# 0001_Page_1.net
KiCad netlist of a schematic drawn in Altium Designer
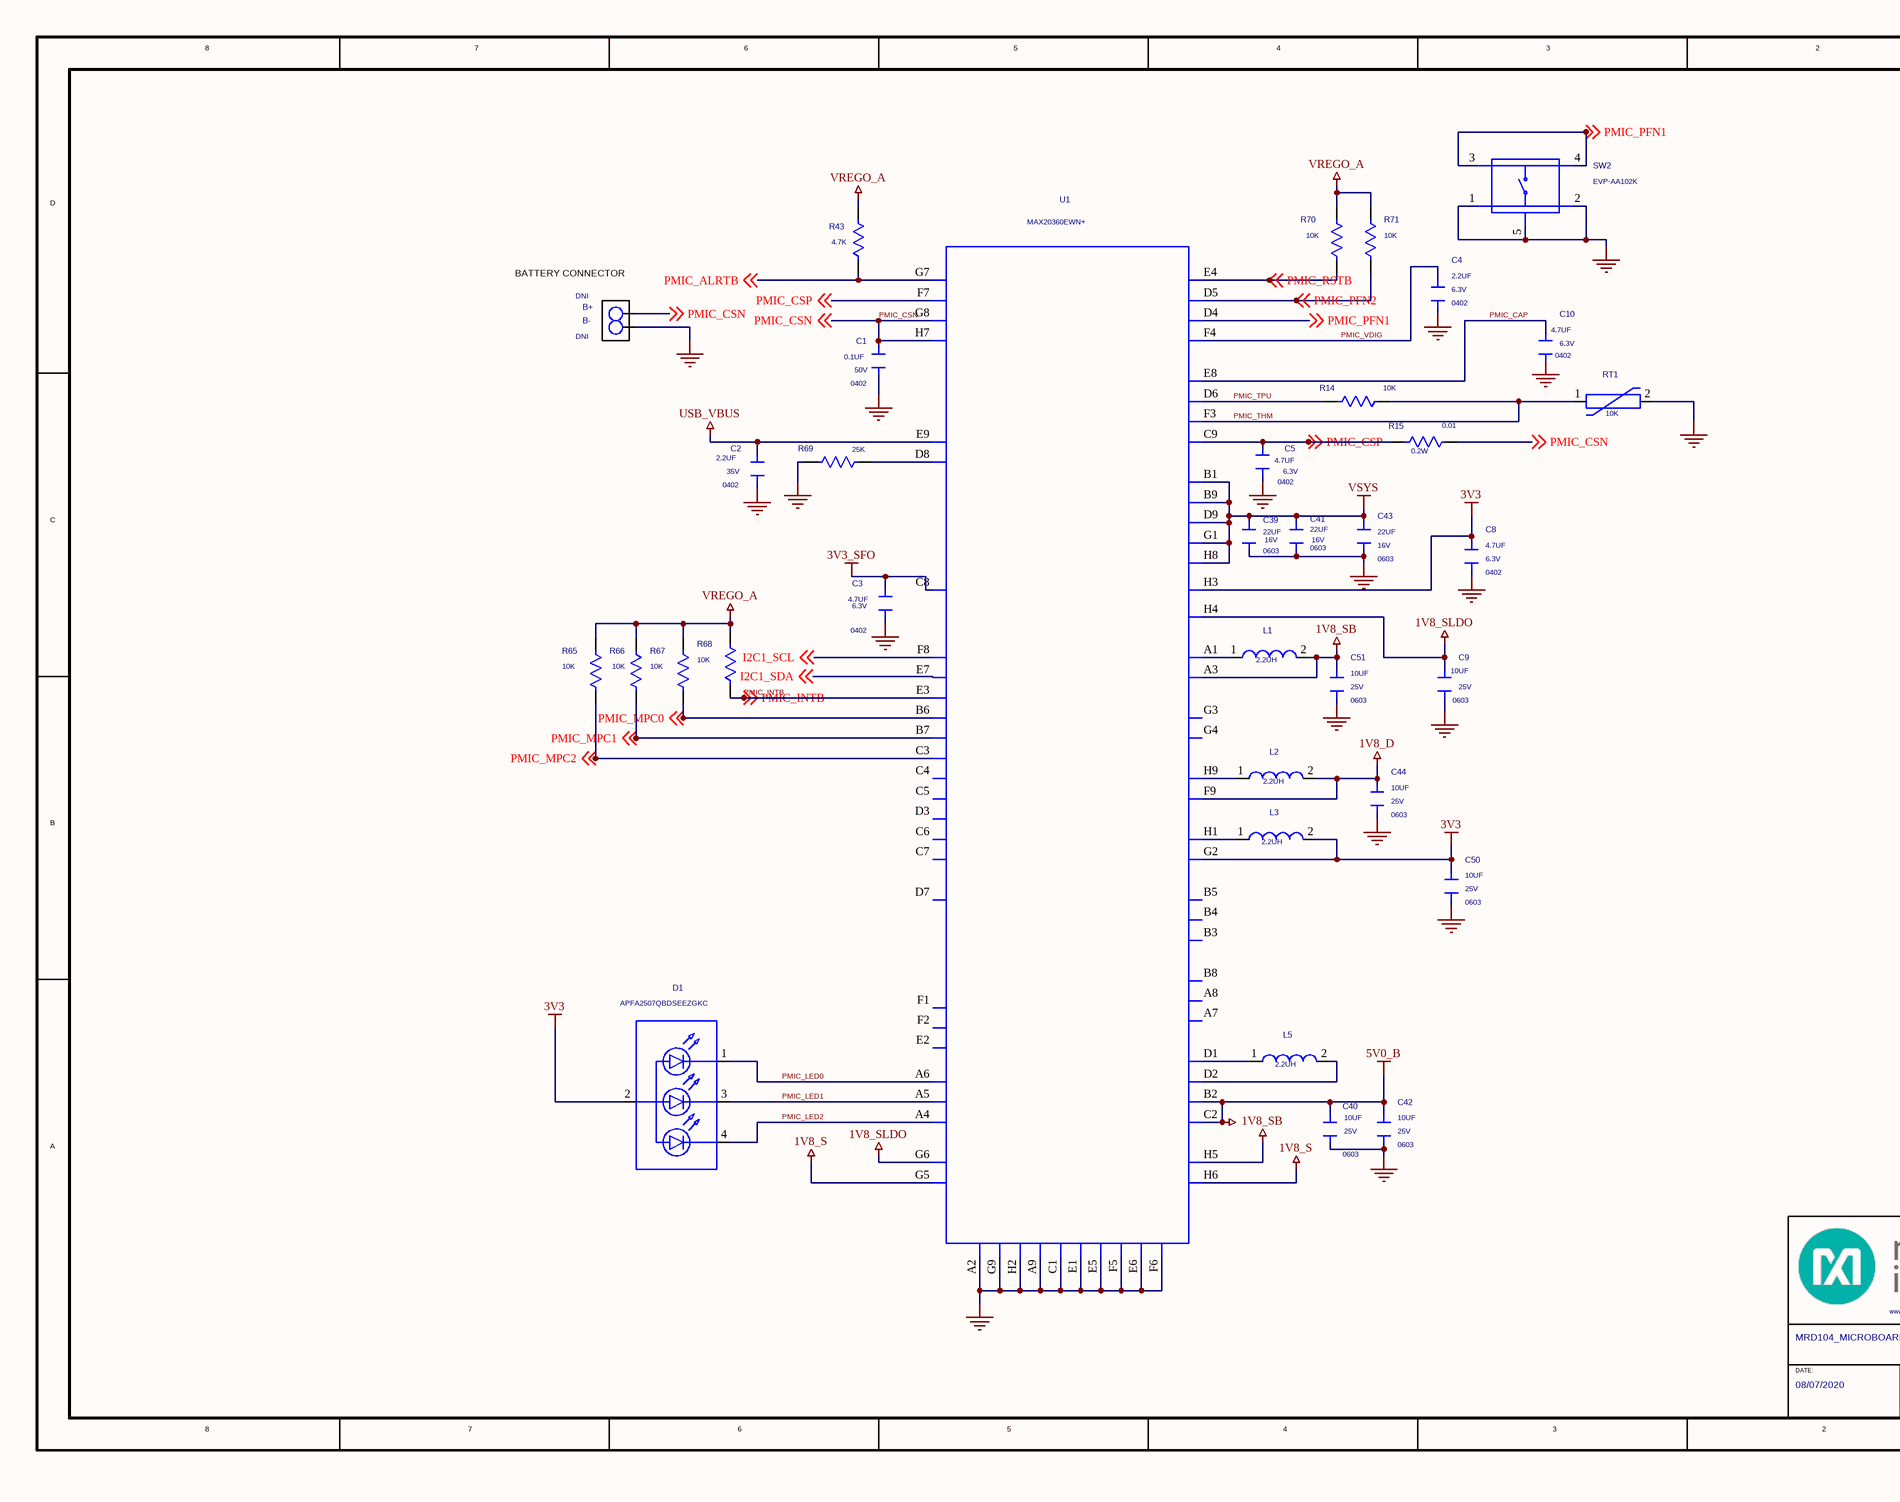
[diagram p0: 0001_Page 1.SchDoc, left]
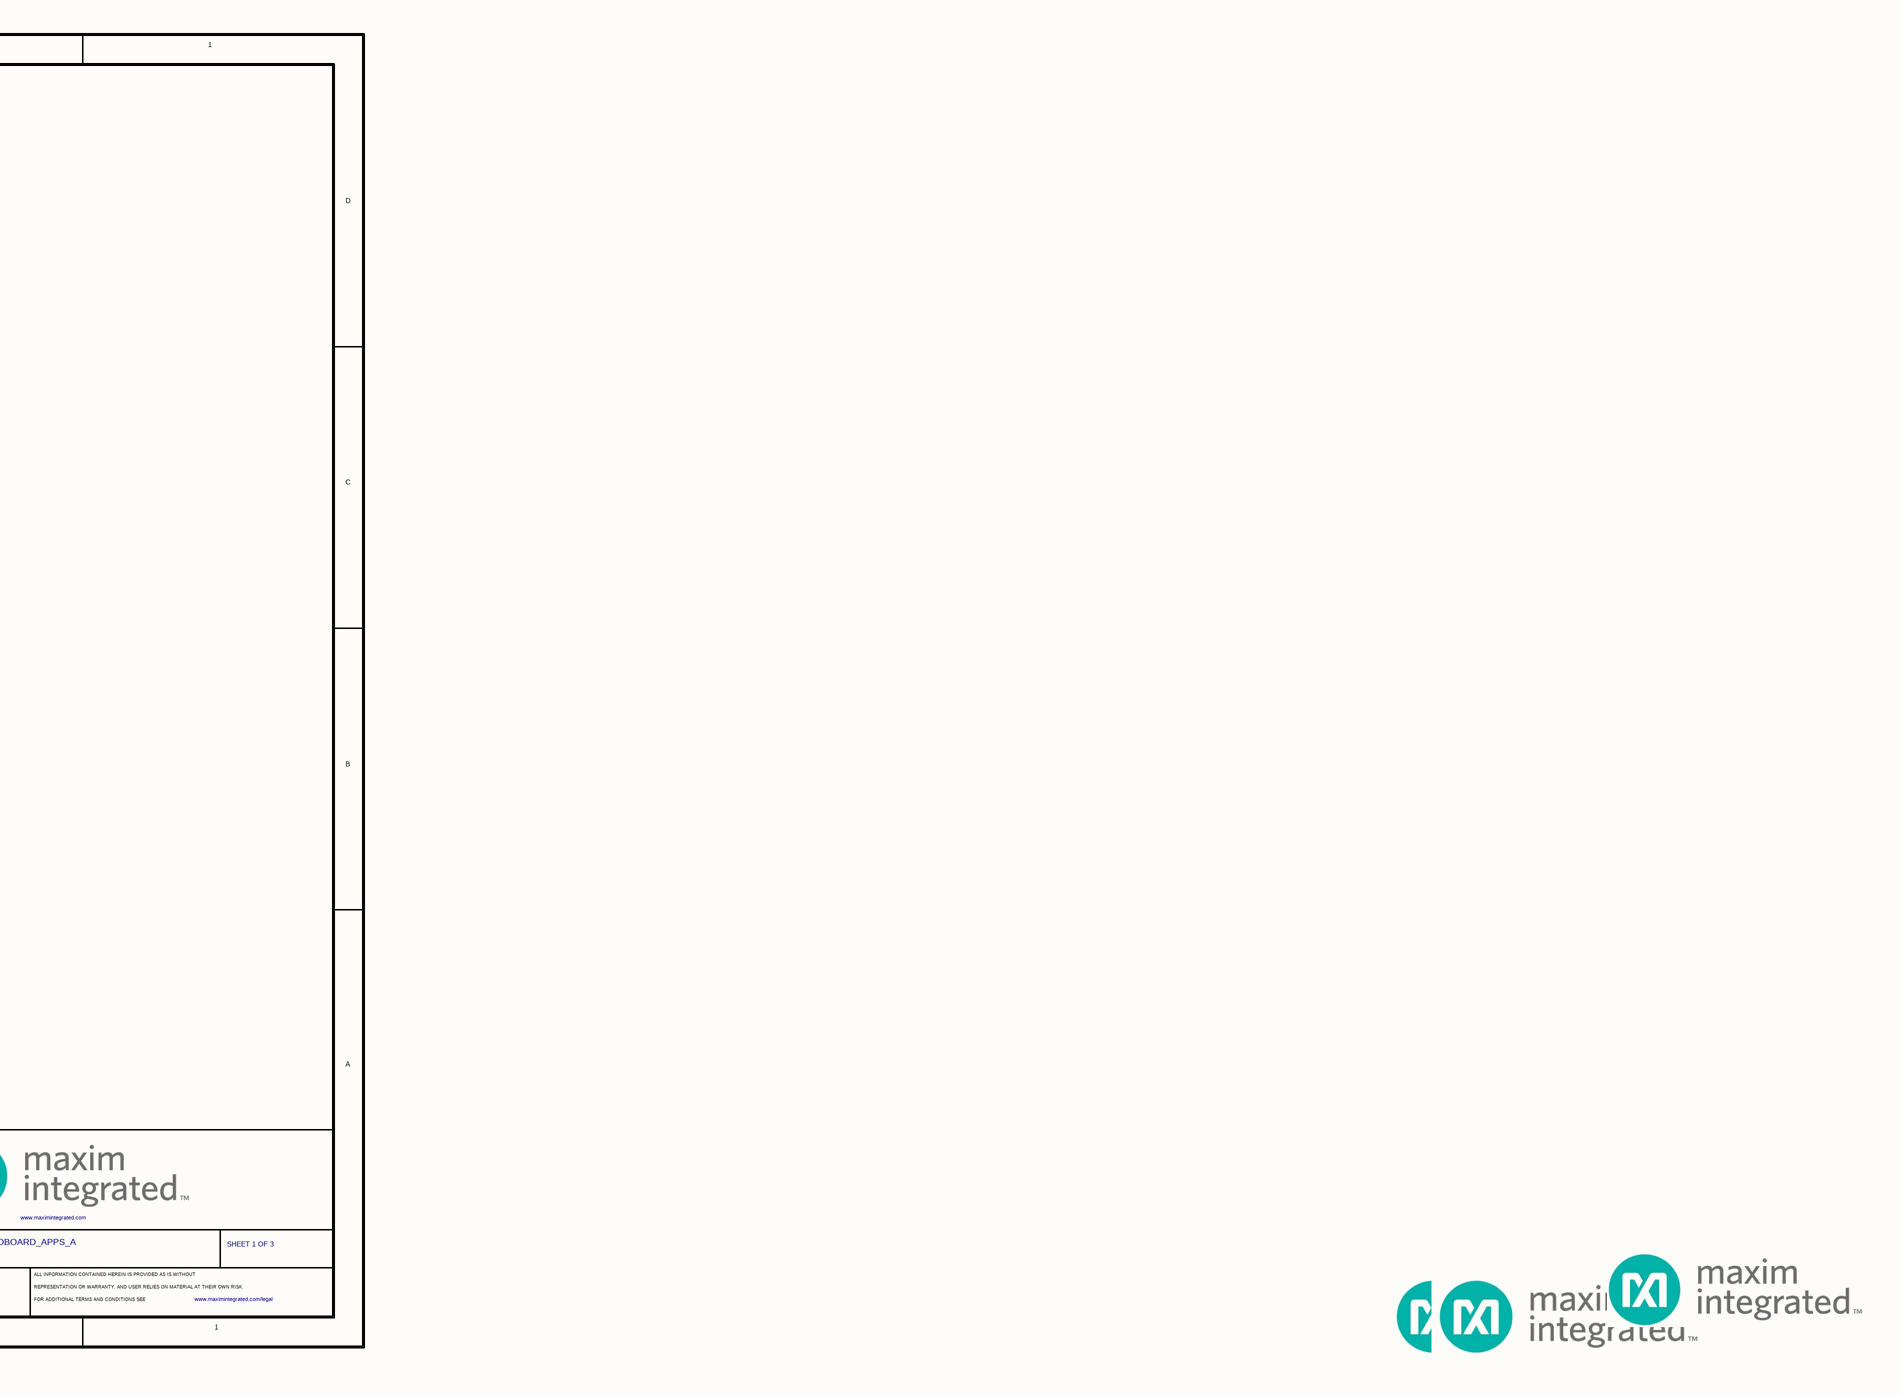
[diagram p1: 0001_Page 1.SchDoc, right]

(export (version "E")
  (design (tool "Eeschema 10.0.6"))
  (components
    (comp (ref "B+")
      (value "N/A")
      (footprint "KEYS_5001")
      (fields
        (field (name "MFG_PART_NUMBER") "5001")
        (field (name "VARIANT") "DNI")
        (field (name "MANUFACTURER") "KEYSTONE")
      )
      (libsource (lib "*") (part "TP"))
    )
    (comp (ref "B-")
      (value "N/A")
      (footprint "KEYS_5001")
      (fields
        (field (name "MFG_PART_NUMBER") "5001")
        (field (name "VARIANT") "DNI")
        (field (name "MANUFACTURER") "KEYSTONE")
      )
      (libsource (lib "*") (part "TP"))
    )
    (comp (ref "C1")
      (value "0.1UF")
      (footprint "0402")
      (description "CAP; SMT (0402); 0.1UF; 10%; 50V; X7R; CERAMIC")
      (fields
        (field (name "PCB FOOTPRINT_CDS") "0402")
        (field (name "TOLERANCE") "10%")
        (field (name "VOLTAGE_RATING") "50V")
        (field (name "MANUFACTURER") "TDK;MURATA;TDK;TAIYO YUDEN")
      )
      (libsource (lib "*") (part "CAP_NP"))
    )
    (comp (ref "C2")
      (value "2.2UF")
      (footprint "0402")
      (description "CAP; SMT (0402); 2.2UF; 10%; 35V; X5R; CERAMIC")
      (fields
        (field (name "PCB FOOTPRINT_CDS") "0402")
        (field (name "MFG_PART_NUMBER") "C1005X5R1V225K050BC")
        (field (name "TOLERANCE") "10%")
        (field (name "VOLTAGE_RATING") "35V")
      )
      (libsource (lib "*") (part "CAP_NP"))
    )
    (comp (ref "C3")
      (value "4.7UF")
      (footprint "0402")
      (description "CAP; SMT (0402); 4.7UF; 10%; 6.3V; X5R; CERAMIC")
      (fields
        (field (name "PCB FOOTPRINT_CDS") "0402")
        (field (name "MFG_PART_NUMBER") "C1005X5R0J475K050BC")
        (field (name "TOLERANCE") "10%")
        (field (name "VOLTAGE_RATING") "6.3V")
      )
      (libsource (lib "*") (part "CAP_NP#1"))
    )
    (comp (ref "C4")
      (value "2.2UF")
      (footprint "0402")
      (description "CAP; SMT (0402); 2.2UF; 10%; 6.3V; X5R; CERAMIC")
      (fields
        (field (name "PCB FOOTPRINT_CDS") "0402")
        (field (name "MFG_PART_NUMBER") "C1005X5R0J225K050BC;CL05A225KQ5NSN")
        (field (name "TOLERANCE") "10%")
        (field (name "VOLTAGE_RATING") "6.3V")
      )
      (libsource (lib "*") (part "CAP_NP"))
    )
    (comp (ref "C5")
      (value "4.7UF")
      (footprint "0402")
      (description "CAP; SMT (0402); 4.7UF; 10%; 6.3V; X5R; CERAMIC")
      (fields
        (field (name "PCB FOOTPRINT_CDS") "0402")
        (field (name "MFG_PART_NUMBER") "C1005X5R0J475K050BC")
        (field (name "TOLERANCE") "10%")
        (field (name "VOLTAGE_RATING") "6.3V")
      )
      (libsource (lib "*") (part "CAP_NP"))
    )
    (comp (ref "C8")
      (value "4.7UF")
      (footprint "0402")
      (description "CAP; SMT (0402); 4.7UF; 10%; 6.3V; X5R; CERAMIC")
      (fields
        (field (name "PCB FOOTPRINT_CDS") "0402")
        (field (name "MFG_PART_NUMBER") "C1005X5R0J475K050BC")
        (field (name "TOLERANCE") "10%")
        (field (name "VOLTAGE_RATING") "6.3V")
      )
      (libsource (lib "*") (part "CAP_NP"))
    )
    (comp (ref "C9")
      (value "10UF")
      (footprint "0603")
      (description "CAP; SMT (0603); 10UF; 20%; 25V; X5R; CERAMIC")
      (fields
        (field (name "PCB FOOTPRINT_CDS") "0603")
        (field (name "MFG_PART_NUMBER") "C1608X5R1E106M080AC;CL10A106MA8NRNC;GRM188R61E106MA73;ZRB18AR61E106ME01;GRT188R61E106ME13")
        (field (name "TOLERANCE") "20%")
        (field (name "VOLTAGE_RATING") "25V")
      )
      (libsource (lib "*") (part "CAP_NP"))
    )
    (comp (ref "C10")
      (value "4.7UF")
      (footprint "0402")
      (description "CAP; SMT (0402); 4.7UF; 10%; 6.3V; X5R; CERAMIC")
      (fields
        (field (name "PCB FOOTPRINT_CDS") "0402")
        (field (name "MFG_PART_NUMBER") "C1005X5R0J475K050BC")
        (field (name "TOLERANCE") "10%")
        (field (name "VOLTAGE_RATING") "6.3V")
      )
      (libsource (lib "*") (part "CAP_NP"))
    )
    (comp (ref "C39")
      (value "22UF")
      (footprint "0603")
      (description "CAP; SMT (0603); 22UF; 20%; 16V; X5R; CERAMIC")
      (fields
        (field (name "PCB FOOTPRINT_CDS") "0603")
        (field (name "MFG_PART_NUMBER") "CL10A226MO7JZNC")
        (field (name "TOLERANCE") "20%")
        (field (name "VOLTAGE_RATING") "16V")
      )
      (libsource (lib "*") (part "CAP_NP"))
    )
    (comp (ref "C40")
      (value "10UF")
      (footprint "0603")
      (description "CAP; SMT (0603); 10UF; 20%; 25V; X5R; CERAMIC")
      (fields
        (field (name "PCB FOOTPRINT_CDS") "0603")
        (field (name "MFG_PART_NUMBER") "C1608X5R1E106M080AC;CL10A106MA8NRNC;GRM188R61E106MA73;ZRB18AR61E106ME01;GRT188R61E106ME13")
        (field (name "TOLERANCE") "20%")
        (field (name "VOLTAGE_RATING") "25V")
      )
      (libsource (lib "*") (part "CAP_NP"))
    )
    (comp (ref "C41")
      (value "22UF")
      (footprint "0603")
      (description "CAP; SMT (0603); 22UF; 20%; 16V; X5R; CERAMIC")
      (fields
        (field (name "PCB FOOTPRINT_CDS") "0603")
        (field (name "MFG_PART_NUMBER") "CL10A226MO7JZNC")
        (field (name "TOLERANCE") "20%")
        (field (name "VOLTAGE_RATING") "16V")
      )
      (libsource (lib "*") (part "CAP_NP"))
    )
    (comp (ref "C42")
      (value "10UF")
      (footprint "0603")
      (description "CAP; SMT (0603); 10UF; 20%; 25V; X5R; CERAMIC")
      (fields
        (field (name "PCB FOOTPRINT_CDS") "0603")
        (field (name "MFG_PART_NUMBER") "C1608X5R1E106M080AC;CL10A106MA8NRNC;GRM188R61E106MA73;ZRB18AR61E106ME01;GRT188R61E106ME13")
        (field (name "TOLERANCE") "20%")
        (field (name "VOLTAGE_RATING") "25V")
      )
      (libsource (lib "*") (part "CAP_NP"))
    )
    (comp (ref "C43")
      (value "22UF")
      (footprint "0603")
      (description "CAP; SMT (0603); 22UF; 20%; 16V; X5R; CERAMIC")
      (fields
        (field (name "PCB FOOTPRINT_CDS") "0603")
        (field (name "MFG_PART_NUMBER") "CL10A226MO7JZNC")
        (field (name "TOLERANCE") "20%")
        (field (name "VOLTAGE_RATING") "16V")
      )
      (libsource (lib "*") (part "CAP_NP"))
    )
    (comp (ref "C44")
      (value "10UF")
      (footprint "0603")
      (description "CAP; SMT (0603); 10UF; 20%; 25V; X5R; CERAMIC")
      (fields
        (field (name "PCB FOOTPRINT_CDS") "0603")
        (field (name "MFG_PART_NUMBER") "C1608X5R1E106M080AC;CL10A106MA8NRNC;GRM188R61E106MA73;ZRB18AR61E106ME01;GRT188R61E106ME13")
        (field (name "TOLERANCE") "20%")
        (field (name "VOLTAGE_RATING") "25V")
      )
      (libsource (lib "*") (part "CAP_NP"))
    )
    (comp (ref "C50")
      (value "10UF")
      (footprint "0603")
      (description "CAP; SMT (0603); 10UF; 20%; 25V; X5R; CERAMIC")
      (fields
        (field (name "PCB FOOTPRINT_CDS") "0603")
        (field (name "MFG_PART_NUMBER") "C1608X5R1E106M080AC;CL10A106MA8NRNC;GRM188R61E106MA73;ZRB18AR61E106ME01;GRT188R61E106ME13")
        (field (name "TOLERANCE") "20%")
        (field (name "VOLTAGE_RATING") "25V")
      )
      (libsource (lib "*") (part "CAP_NP"))
    )
    (comp (ref "C51")
      (value "10UF")
      (footprint "0603")
      (description "CAP; SMT (0603); 10UF; 20%; 25V; X5R; CERAMIC")
      (fields
        (field (name "PCB FOOTPRINT_CDS") "0603")
        (field (name "MFG_PART_NUMBER") "C1608X5R1E106M080AC;CL10A106MA8NRNC;GRM188R61E106MA73;ZRB18AR61E106ME01;GRT188R61E106ME13")
        (field (name "TOLERANCE") "20%")
        (field (name "VOLTAGE_RATING") "25V")
      )
      (libsource (lib "*") (part "CAP_NP"))
    )
    (comp (ref "D1")
      (value "APFA2507QBDSEEZGKC")
      (footprint "LED_APFA2507")
      (fields (field (name "MANUFACTURER") "KINGBRIGHT"))
      (libsource (lib "*") (part "LED_4P"))
    )
    (comp (ref "L1")
      (value "2.2UH")
      (footprint "IND_2016")
      (description "INDUCTOR; SMT (0806); WIREWOUND CHIP; 2.2UH; TOL=+/-20%; 1.8A")
      (fields (field (name "MFG_PART_NUMBER") "DFE201612E-2R2M") (field (name "TOLERANCE") "20%"))
      (libsource (lib "*") (part "INDUCT"))
    )
    (comp (ref "L2")
      (value "2.2UH")
      (footprint "IND_2016")
      (description "INDUCTOR; SMT (0806); WIREWOUND CHIP; 2.2UH; TOL=+/-20%; 1.8A")
      (fields (field (name "MFG_PART_NUMBER") "DFE201612E-2R2M") (field (name "TOLERANCE") "20%"))
      (libsource (lib "*") (part "INDUCT"))
    )
    (comp (ref "L3")
      (value "2.2UH")
      (footprint "IND_2016")
      (description "INDUCTOR; SMT (0806); WIREWOUND CHIP; 2.2UH; TOL=+/-20%; 1.8A")
      (fields (field (name "MFG_PART_NUMBER") "DFE201612E-2R2M") (field (name "TOLERANCE") "20%"))
      (libsource (lib "*") (part "INDUCT"))
    )
    (comp (ref "L5")
      (value "2.2UH")
      (footprint "IND_2016")
      (description "INDUCTOR; SMT (0806); WIREWOUND CHIP; 2.2UH; TOL=+/-20%; 1.8A")
      (fields (field (name "MFG_PART_NUMBER") "DFE201612E-2R2M") (field (name "TOLERANCE") "20%"))
      (libsource (lib "*") (part "INDUCT"))
    )
    (comp (ref "R14")
      (value "10K")
      (footprint "0402")
      (description "RES; SMT (0402); 10K; 5%; +/-200PPM/DEGC; 0.1000W")
      (fields (field (name "MFG_PART_NUMBER") "ERJ-2GEJ103") (field (name "TOLERANCE") "5%"))
      (libsource (lib "*") (part "RES_SMD#1"))
    )
    (comp (ref "R15")
      (value "0.01")
      (footprint "0402")
      (description "RES; SMT (0402); 0.01; 1%; 0 TO +500PPM/DEGC; 0.2000W")
      (fields
        (field (name "MFG_PART_NUMBER") "ERJ-2LWFR010")
        (field (name "POWER_RATING") "0.2W")
        (field (name "TOLERANCE") "1%")
      )
      (libsource (lib "*") (part "RES_SMD#1"))
    )
    (comp (ref "R43")
      (value "4.7K")
      (footprint "0402")
      (description "RES; SMT (0402); 4.7K; 1%; +/-100PPM/DEGC; 0.0630W")
      (fields (field (name "MFG_PART_NUMBER") "CRCW04024K70FK;MCR01MZPF4701") (field (name "TOLERANCE") "1%"))
      (libsource (lib "*") (part "RES_SMD"))
    )
    (comp (ref "R65")
      (value "10K")
      (footprint "0402")
      (description "RES; SMT (0402); 10K; 1%; +/-100PPM/DEGC; 0.0630W")
      (fields
        (field (name "MFG_PART_NUMBER") "CRCW040210K0FK;RC0402FR-0710KL")
        (field (name "TOLERANCE") "1%")
      )
      (libsource (lib "*") (part "RES_SMD"))
    )
    (comp (ref "R66")
      (value "10K")
      (footprint "0402")
      (description "RES; SMT (0402); 10K; 1%; +/-100PPM/DEGC; 0.0630W")
      (fields
        (field (name "MFG_PART_NUMBER") "CRCW040210K0FK;RC0402FR-0710KL")
        (field (name "TOLERANCE") "1%")
      )
      (libsource (lib "*") (part "RES_SMD"))
    )
    (comp (ref "R67")
      (value "10K")
      (footprint "0402")
      (description "RES; SMT (0402); 10K; 1%; +/-100PPM/DEGC; 0.0630W")
      (fields
        (field (name "MFG_PART_NUMBER") "CRCW040210K0FK;RC0402FR-0710KL")
        (field (name "TOLERANCE") "1%")
      )
      (libsource (lib "*") (part "RES_SMD"))
    )
    (comp (ref "R68")
      (value "10K")
      (footprint "0402")
      (description "RES; SMT (0402); 10K; 1%; +/-100PPM/DEGC; 0.0630W")
      (fields
        (field (name "MFG_PART_NUMBER") "CRCW040210K0FK;RC0402FR-0710KL")
        (field (name "TOLERANCE") "1%")
      )
      (libsource (lib "*") (part "RES_SMD"))
    )
    (comp (ref "R69")
      (value "25K")
      (footprint "0402")
      (description "RES; SMT (0402); 25K; 0.10%; +/-25PPM/DEGK; 0.0500W")
      (fields (field (name "MFG_PART_NUMBER") "PNM0402E2502BS") (field (name "TOLERANCE") "0.1%"))
      (libsource (lib "*") (part "RES_SMD"))
    )
    (comp (ref "R70")
      (value "10K")
      (footprint "0402")
      (description "RES; SMT (0402); 10K; 1%; +/-100PPM/DEGC; 0.0630W")
      (fields
        (field (name "MFG_PART_NUMBER") "CRCW040210K0FK;RC0402FR-0710KL")
        (field (name "TOLERANCE") "1%")
      )
      (libsource (lib "*") (part "RES_SMD"))
    )
    (comp (ref "R71")
      (value "10K")
      (footprint "0402")
      (description "RES; SMT (0402); 10K; 1%; +/-100PPM/DEGC; 0.0630W")
      (fields
        (field (name "MFG_PART_NUMBER") "CRCW040210K0FK;RC0402FR-0710KL")
        (field (name "TOLERANCE") "1%")
      )
      (libsource (lib "*") (part "RES_SMD"))
    )
    (comp (ref "RT1")
      (value "10K")
      (footprint "THRMC0603X33M")
      (description "THERMISTOR; SMT (0201); 10K OHM; TOL=+/-5%")
      (fields (field (name "MFG_PART_NUMBER") "NCP03XH103J05") (field (name "TOLERANCE") "5%"))
      (libsource (lib "*") (part "THERMISTOR_SMD"))
    )
    (comp (ref "SW2")
      (value "EVP-AA102K")
      (footprint "SW_EVP-AAX02X_GND")
      (fields (field (name "MANUFACTURER") "PANASONIC"))
      (libsource (lib "*") (part "EVP-AAXXXX"))
    )
    (comp (ref "U1")
      (value "MAX20360EWN+")
      (footprint "MAXIM_21-100373")
      (fields (field (name "MANUFACTURER") "MAXIM"))
      (libsource (lib "*") (part "EK_MAX20360"))
    )
  )
  (nets
    (net (code "1") (name "/PMIC_CAP") (class "Default")
      (node (ref "C10") (pin "2") (pinfunction "2_2") (pintype "bidirectional"))
      (node (ref "U1") (pin "E8") (pinfunction "E8_E8") (pintype "bidirectional"))
    )
    (net (code "2") (name "/PMIC_LED0") (class "Default")
      (node (ref "D1") (pin "1") (pinfunction "K1_1") (pintype "bidirectional"))
      (node (ref "U1") (pin "A6") (pinfunction "A6_A6") (pintype "bidirectional"))
    )
    (net (code "3") (name "/PMIC_LED1") (class "Default")
      (node (ref "D1") (pin "3") (pinfunction "K2_3") (pintype "bidirectional"))
      (node (ref "U1") (pin "A5") (pinfunction "A5_A5") (pintype "bidirectional"))
    )
    (net (code "4") (name "/PMIC_LED2") (class "Default")
      (node (ref "D1") (pin "4") (pinfunction "K3_4") (pintype "bidirectional"))
      (node (ref "U1") (pin "A4") (pinfunction "A4_A4") (pintype "bidirectional"))
    )
    (net (code "5") (name "/PMIC_THM") (class "Default")
      (node (ref "R14") (pin "2") (pinfunction "2_2") (pintype "bidirectional"))
      (node (ref "RT1") (pin "1") (pinfunction "1_1") (pintype "bidirectional"))
      (node (ref "U1") (pin "F3") (pinfunction "F3_F3") (pintype "bidirectional"))
    )
    (net (code "6") (name "/PMIC_TPU") (class "Default")
      (node (ref "R14") (pin "1") (pinfunction "1_1") (pintype "bidirectional"))
      (node (ref "U1") (pin "D6") (pinfunction "D6_D6") (pintype "bidirectional"))
    )
    (net (code "7") (name "/PMIC_VDIG") (class "Default")
      (node (ref "C4") (pin "2") (pinfunction "2_2") (pintype "bidirectional"))
      (node (ref "U1") (pin "F4") (pinfunction "F4_F4") (pintype "bidirectional"))
    )
    (net (code "8") (name "1V8_D") (class "Default")
      (node (ref "C44") (pin "2") (pinfunction "2_2") (pintype "bidirectional"))
      (node (ref "L2") (pin "2") (pinfunction "2_2") (pintype "bidirectional"))
      (node (ref "U1") (pin "F9") (pinfunction "F9_F9") (pintype "bidirectional"))
    )
    (net (code "9") (name "1V8_S") (class "Default")
      (node (ref "U1") (pin "G5") (pinfunction "G5_G5") (pintype "bidirectional"))
      (node (ref "U1") (pin "H6") (pinfunction "H6_H6") (pintype "bidirectional"))
    )
    (net (code "10") (name "1V8_SB") (class "Default")
      (node (ref "C51") (pin "2") (pinfunction "2_2") (pintype "bidirectional"))
      (node (ref "L1") (pin "2") (pinfunction "2_2") (pintype "bidirectional"))
      (node (ref "U1") (pin "A3") (pinfunction "A3_A3") (pintype "bidirectional"))
      (node (ref "U1") (pin "H5") (pinfunction "H5_H5") (pintype "bidirectional"))
    )
    (net (code "11") (name "1V8_SLDO") (class "Default")
      (node (ref "C9") (pin "2") (pinfunction "2_2") (pintype "bidirectional"))
      (node (ref "U1") (pin "G6") (pinfunction "G6_G6") (pintype "bidirectional"))
      (node (ref "U1") (pin "H4") (pinfunction "H4_H4") (pintype "bidirectional"))
    )
    (net (code "12") (name "3V3") (class "Default")
      (node (ref "C50") (pin "2") (pinfunction "2_2") (pintype "bidirectional"))
      (node (ref "C8") (pin "2") (pinfunction "2_2") (pintype "bidirectional"))
      (node (ref "D1") (pin "2") (pinfunction "A_2") (pintype "bidirectional"))
      (node (ref "L3") (pin "2") (pinfunction "2_2") (pintype "bidirectional"))
      (node (ref "U1") (pin "G2") (pinfunction "G2_G2") (pintype "bidirectional"))
      (node (ref "U1") (pin "H3") (pinfunction "H3_H3") (pintype "bidirectional"))
    )
    (net (code "13") (name "3V3_SFO") (class "Default")
      (node (ref "C3") (pin "1") (pinfunction "1_1") (pintype "bidirectional"))
      (node (ref "U1") (pin "C8") (pinfunction "C8_C8") (pintype "bidirectional"))
    )
    (net (code "14") (name "5V0_B") (class "Default")
      (node (ref "C40") (pin "2") (pinfunction "2_2") (pintype "bidirectional"))
      (node (ref "C42") (pin "2") (pinfunction "2_2") (pintype "bidirectional"))
      (node (ref "U1") (pin "B2") (pinfunction "B2_B2") (pintype "bidirectional"))
      (node (ref "U1") (pin "C2") (pinfunction "C2_C2") (pintype "bidirectional"))
    )
    (net (code "15") (name "GND_POWER") (class "Default")
      (node (ref "B-") (pin "1") (pinfunction "TP1_1") (pintype "bidirectional"))
      (node (ref "C1") (pin "1") (pinfunction "1_1") (pintype "bidirectional"))
      (node (ref "C10") (pin "1") (pinfunction "1_1") (pintype "bidirectional"))
      (node (ref "C2") (pin "1") (pinfunction "1_1") (pintype "bidirectional"))
      (node (ref "C3") (pin "2") (pinfunction "2_2") (pintype "bidirectional"))
      (node (ref "C39") (pin "1") (pinfunction "1_1") (pintype "bidirectional"))
      (node (ref "C4") (pin "1") (pinfunction "1_1") (pintype "bidirectional"))
      (node (ref "C40") (pin "1") (pinfunction "1_1") (pintype "bidirectional"))
      (node (ref "C41") (pin "1") (pinfunction "1_1") (pintype "bidirectional"))
      (node (ref "C42") (pin "1") (pinfunction "1_1") (pintype "bidirectional"))
      (node (ref "C43") (pin "1") (pinfunction "1_1") (pintype "bidirectional"))
      (node (ref "C44") (pin "1") (pinfunction "1_1") (pintype "bidirectional"))
      (node (ref "C5") (pin "1") (pinfunction "1_1") (pintype "bidirectional"))
      (node (ref "C50") (pin "1") (pinfunction "1_1") (pintype "bidirectional"))
      (node (ref "C51") (pin "1") (pinfunction "1_1") (pintype "bidirectional"))
      (node (ref "C8") (pin "1") (pinfunction "1_1") (pintype "bidirectional"))
      (node (ref "C9") (pin "1") (pinfunction "1_1") (pintype "bidirectional"))
      (node (ref "R69") (pin "1") (pinfunction "1_1") (pintype "bidirectional"))
      (node (ref "RT1") (pin "2") (pinfunction "2_2") (pintype "bidirectional"))
      (node (ref "SW2") (pin "1") (pinfunction "1_1") (pintype "bidirectional"))
      (node (ref "SW2") (pin "2") (pinfunction "2_2") (pintype "bidirectional"))
      (node (ref "SW2") (pin "5") (pinfunction "5_5") (pintype "bidirectional"))
      (node (ref "U1") (pin "A2") (pinfunction "A2_A2") (pintype "bidirectional"))
      (node (ref "U1") (pin "A9") (pinfunction "A9_A9") (pintype "bidirectional"))
      (node (ref "U1") (pin "C1") (pinfunction "C1_C1") (pintype "bidirectional"))
      (node (ref "U1") (pin "E1") (pinfunction "E1_E1") (pintype "bidirectional"))
      (node (ref "U1") (pin "E5") (pinfunction "E5_E5") (pintype "bidirectional"))
      (node (ref "U1") (pin "E6") (pinfunction "E6_E6") (pintype "bidirectional"))
      (node (ref "U1") (pin "F5") (pinfunction "F5_F5") (pintype "bidirectional"))
      (node (ref "U1") (pin "F6") (pinfunction "F6_F6") (pintype "bidirectional"))
      (node (ref "U1") (pin "G9") (pinfunction "G9_G9") (pintype "bidirectional"))
      (node (ref "U1") (pin "H2") (pinfunction "H2_H2") (pintype "bidirectional"))
    )
    (net (code "16") (name "I2C1_SCL") (class "Default")
      (node (ref "U1") (pin "F8") (pinfunction "F8_F8") (pintype "bidirectional"))
    )
    (net (code "17") (name "I2C1_SDA") (class "Default")
      (node (ref "U1") (pin "E7") (pinfunction "E7_E7") (pintype "bidirectional"))
    )
    (net (code "18") (name "Net-(L1-Pad1)") (class "Default")
      (node (ref "L1") (pin "1") (pinfunction "1_1") (pintype "bidirectional"))
      (node (ref "U1") (pin "A1") (pinfunction "A1_A1") (pintype "bidirectional"))
    )
    (net (code "19") (name "Net-(L2-Pad1)") (class "Default")
      (node (ref "L2") (pin "1") (pinfunction "1_1") (pintype "bidirectional"))
      (node (ref "U1") (pin "H9") (pinfunction "H9_H9") (pintype "bidirectional"))
    )
    (net (code "20") (name "Net-(L3-Pad1)") (class "Default")
      (node (ref "L3") (pin "1") (pinfunction "1_1") (pintype "bidirectional"))
      (node (ref "U1") (pin "H1") (pinfunction "H1_H1") (pintype "bidirectional"))
    )
    (net (code "21") (name "Net-(L5-Pad1)") (class "Default")
      (node (ref "L5") (pin "1") (pinfunction "1_1") (pintype "bidirectional"))
      (node (ref "U1") (pin "D1") (pinfunction "D1_D1") (pintype "bidirectional"))
    )
    (net (code "22") (name "Net-(L5-Pad2)") (class "Default")
      (node (ref "L5") (pin "2") (pinfunction "2_2") (pintype "bidirectional"))
      (node (ref "U1") (pin "D2") (pinfunction "D2_D2") (pintype "bidirectional"))
    )
    (net (code "23") (name "Net-(R69-Pad2)") (class "Default")
      (node (ref "R69") (pin "2") (pinfunction "2_2") (pintype "bidirectional"))
      (node (ref "U1") (pin "D8") (pinfunction "D8_D8") (pintype "bidirectional"))
    )
    (net (code "24") (name "PMIC_ALRTB") (class "Default")
      (node (ref "R43") (pin "1") (pinfunction "1_1") (pintype "bidirectional"))
      (node (ref "U1") (pin "G7") (pinfunction "G7_G7") (pintype "bidirectional"))
    )
    (net (code "25") (name "PMIC_CSN") (class "Default")
      (node (ref "B+") (pin "1") (pinfunction "TP1_1") (pintype "bidirectional"))
      (node (ref "C1") (pin "2") (pinfunction "2_2") (pintype "bidirectional"))
      (node (ref "R15") (pin "2") (pinfunction "2_2") (pintype "bidirectional"))
      (node (ref "U1") (pin "G8") (pinfunction "G8_G8") (pintype "bidirectional"))
      (node (ref "U1") (pin "H7") (pinfunction "H7_H7") (pintype "bidirectional"))
    )
    (net (code "26") (name "PMIC_CSP") (class "Default")
      (node (ref "C5") (pin "2") (pinfunction "2_2") (pintype "bidirectional"))
      (node (ref "R15") (pin "1") (pinfunction "1_1") (pintype "bidirectional"))
      (node (ref "U1") (pin "C9") (pinfunction "C9_C9") (pintype "bidirectional"))
      (node (ref "U1") (pin "F7") (pinfunction "F7_F7") (pintype "bidirectional"))
    )
    (net (code "27") (name "PMIC_INTB") (class "Default")
      (node (ref "R68") (pin "1") (pinfunction "1_1") (pintype "bidirectional"))
      (node (ref "U1") (pin "E3") (pinfunction "E3_E3") (pintype "bidirectional"))
    )
    (net (code "28") (name "PMIC_MPC0") (class "Default")
      (node (ref "R67") (pin "1") (pinfunction "1_1") (pintype "bidirectional"))
      (node (ref "U1") (pin "B6") (pinfunction "B6_B6") (pintype "bidirectional"))
    )
    (net (code "29") (name "PMIC_MPC1") (class "Default")
      (node (ref "R66") (pin "1") (pinfunction "1_1") (pintype "bidirectional"))
      (node (ref "U1") (pin "B7") (pinfunction "B7_B7") (pintype "bidirectional"))
    )
    (net (code "30") (name "PMIC_MPC2") (class "Default")
      (node (ref "R65") (pin "1") (pinfunction "1_1") (pintype "bidirectional"))
      (node (ref "U1") (pin "C3") (pinfunction "C3_C3") (pintype "bidirectional"))
    )
    (net (code "31") (name "PMIC_PFN1") (class "Default")
      (node (ref "SW2") (pin "3") (pinfunction "3_3") (pintype "bidirectional"))
      (node (ref "SW2") (pin "4") (pinfunction "4_4") (pintype "bidirectional"))
      (node (ref "U1") (pin "D4") (pinfunction "D4_D4") (pintype "bidirectional"))
    )
    (net (code "32") (name "PMIC_PFN2") (class "Default")
      (node (ref "R71") (pin "1") (pinfunction "1_1") (pintype "bidirectional"))
      (node (ref "U1") (pin "D5") (pinfunction "D5_D5") (pintype "bidirectional"))
    )
    (net (code "33") (name "PMIC_RSTB") (class "Default")
      (node (ref "R70") (pin "1") (pinfunction "1_1") (pintype "bidirectional"))
      (node (ref "U1") (pin "E4") (pinfunction "E4_E4") (pintype "bidirectional"))
    )
    (net (code "34") (name "USB_VBUS") (class "Default")
      (node (ref "C2") (pin "2") (pinfunction "2_2") (pintype "bidirectional"))
      (node (ref "U1") (pin "E9") (pinfunction "E9_E9") (pintype "bidirectional"))
    )
    (net (code "35") (name "VREGO_A") (class "Default")
      (node (ref "R43") (pin "2") (pinfunction "2_2") (pintype "bidirectional"))
      (node (ref "R65") (pin "2") (pinfunction "2_2") (pintype "bidirectional"))
      (node (ref "R66") (pin "2") (pinfunction "2_2") (pintype "bidirectional"))
      (node (ref "R67") (pin "2") (pinfunction "2_2") (pintype "bidirectional"))
      (node (ref "R68") (pin "2") (pinfunction "2_2") (pintype "bidirectional"))
      (node (ref "R70") (pin "2") (pinfunction "2_2") (pintype "bidirectional"))
      (node (ref "R71") (pin "2") (pinfunction "2_2") (pintype "bidirectional"))
    )
    (net (code "36") (name "VSYS") (class "Default")
      (node (ref "C39") (pin "2") (pinfunction "2_2") (pintype "bidirectional"))
      (node (ref "C41") (pin "2") (pinfunction "2_2") (pintype "bidirectional"))
      (node (ref "C43") (pin "2") (pinfunction "2_2") (pintype "bidirectional"))
      (node (ref "U1") (pin "B1") (pinfunction "B1_B1") (pintype "bidirectional"))
      (node (ref "U1") (pin "B9") (pinfunction "B9_B9") (pintype "bidirectional"))
      (node (ref "U1") (pin "D9") (pinfunction "D9_D9") (pintype "bidirectional"))
      (node (ref "U1") (pin "G1") (pinfunction "G1_G1") (pintype "bidirectional"))
      (node (ref "U1") (pin "H8") (pinfunction "H8_H8") (pintype "bidirectional"))
    )
    (net (code "37") (name "unconnected-(U1-PadA7)") (class "Default")
      (node (ref "U1") (pin "A7") (pinfunction "A7_A7") (pintype "bidirectional"))
    )
    (net (code "38") (name "unconnected-(U1-PadA8)") (class "Default")
      (node (ref "U1") (pin "A8") (pinfunction "A8_A8") (pintype "bidirectional"))
    )
    (net (code "39") (name "unconnected-(U1-PadB3)") (class "Default")
      (node (ref "U1") (pin "B3") (pinfunction "B3_B3") (pintype "bidirectional"))
    )
    (net (code "40") (name "unconnected-(U1-PadB4)") (class "Default")
      (node (ref "U1") (pin "B4") (pinfunction "B4_B4") (pintype "bidirectional"))
    )
    (net (code "41") (name "unconnected-(U1-PadB5)") (class "Default")
      (node (ref "U1") (pin "B5") (pinfunction "B5_B5") (pintype "bidirectional"))
    )
    (net (code "42") (name "unconnected-(U1-PadB8)") (class "Default")
      (node (ref "U1") (pin "B8") (pinfunction "B8_B8") (pintype "bidirectional"))
    )
    (net (code "43") (name "unconnected-(U1-PadC4)") (class "Default")
      (node (ref "U1") (pin "C4") (pinfunction "C4_C4") (pintype "bidirectional"))
    )
    (net (code "44") (name "unconnected-(U1-PadC5)") (class "Default")
      (node (ref "U1") (pin "C5") (pinfunction "C5_C5") (pintype "bidirectional"))
    )
    (net (code "45") (name "unconnected-(U1-PadC6)") (class "Default")
      (node (ref "U1") (pin "C6") (pinfunction "C6_C6") (pintype "bidirectional"))
    )
    (net (code "46") (name "unconnected-(U1-PadC7)") (class "Default")
      (node (ref "U1") (pin "C7") (pinfunction "C7_C7") (pintype "bidirectional"))
    )
    (net (code "47") (name "unconnected-(U1-PadD3)") (class "Default")
      (node (ref "U1") (pin "D3") (pinfunction "D3_D3") (pintype "bidirectional"))
    )
    (net (code "48") (name "unconnected-(U1-PadD7)") (class "Default")
      (node (ref "U1") (pin "D7") (pinfunction "D7_D7") (pintype "bidirectional"))
    )
    (net (code "49") (name "unconnected-(U1-PadE2)") (class "Default")
      (node (ref "U1") (pin "E2") (pinfunction "E2_E2") (pintype "bidirectional"))
    )
    (net (code "50") (name "unconnected-(U1-PadF1)") (class "Default")
      (node (ref "U1") (pin "F1") (pinfunction "F1_F1") (pintype "bidirectional"))
    )
    (net (code "51") (name "unconnected-(U1-PadF2)") (class "Default")
      (node (ref "U1") (pin "F2") (pinfunction "F2_F2") (pintype "bidirectional"))
    )
    (net (code "52") (name "unconnected-(U1-PadG3)") (class "Default")
      (node (ref "U1") (pin "G3") (pinfunction "G3_G3") (pintype "bidirectional"))
    )
    (net (code "53") (name "unconnected-(U1-PadG4)") (class "Default")
      (node (ref "U1") (pin "G4") (pinfunction "G4_G4") (pintype "bidirectional"))
    )
  )
)
